# larson.net
KiCad netlist of a schematic drawn in EAGLE
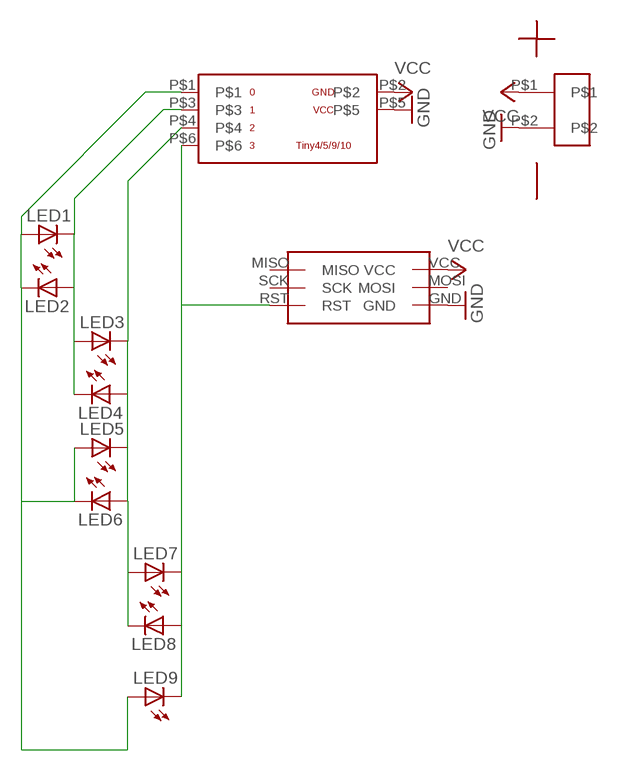
[diagram p0: schematic, sheet 1]

(export (version "E")
  (design (tool "Eeschema 10.0.6"))
  (components
    (comp (ref "LED1")
      (value "LED3MM")
      (footprint "eagle-import:LED3MM")
      (libsource (lib "eagle-import") (part "LED3MM"))
    )
    (comp (ref "LED2")
      (value "LED3MM")
      (footprint "eagle-import:LED3MM")
      (libsource (lib "eagle-import") (part "LED3MM"))
    )
    (comp (ref "LED3")
      (value "LED3MM")
      (footprint "eagle-import:LED3MM")
      (libsource (lib "eagle-import") (part "LED3MM"))
    )
    (comp (ref "LED4")
      (value "LED3MM")
      (footprint "eagle-import:LED3MM")
      (libsource (lib "eagle-import") (part "LED3MM"))
    )
    (comp (ref "LED5")
      (value "LED3MM")
      (footprint "eagle-import:LED3MM")
      (libsource (lib "eagle-import") (part "LED3MM"))
    )
    (comp (ref "LED6")
      (value "LED3MM")
      (footprint "eagle-import:LED3MM")
      (libsource (lib "eagle-import") (part "LED3MM"))
    )
    (comp (ref "LED7")
      (value "LED3MM")
      (footprint "eagle-import:LED3MM")
      (libsource (lib "eagle-import") (part "LED3MM"))
    )
    (comp (ref "LED8")
      (value "LED3MM")
      (footprint "eagle-import:LED3MM")
      (libsource (lib "eagle-import") (part "LED3MM"))
    )
    (comp (ref "LED9")
      (value "LED3MM")
      (footprint "eagle-import:LED3MM")
      (libsource (lib "eagle-import") (part "LED3MM"))
    )
    (comp (ref "U$1")
      (value "ATTINY4/5/9/10")
      (footprint "eagle-import:SOT23-6ST1")
      (libsource (lib "eagle-import") (part "ATTINY4/5/9/10"))
    )
    (comp (ref "U$2")
      (value "POWER_PINS")
      (footprint "eagle-import:POWER_PINS")
      (libsource (lib "eagle-import") (part "POWER_PINS"))
    )
    (comp (ref "U$3")
      (value "AVR_ISP_6_PIN_1X6_SMT_CONTACT_BIG")
      (footprint "eagle-import:CONTACT_ISP_PROGRAMMER_1X6_ATMEL")
      (libsource (lib "eagle-import") (part "AVR_ISP_6_PIN_1X6_SMT_CONTACT_BIG"))
    )
  )
  (nets
    (net (code "1") (name "GND") (class "Default")
      (node (ref "U$1") (pin "P$5") (pinfunction "P$5_P$5") (pintype "bidirectional"))
      (node (ref "U$2") (pin "P$2") (pinfunction "P$2_P$2") (pintype "bidirectional"))
      (node (ref "U$3") (pin "GND") (pinfunction "GND_GND") (pintype "bidirectional"))
    )
    (net (code "2") (name "Net-(LED1-C)") (class "Default")
      (node (ref "LED1") (pin "K") (pinfunction "C_K") (pintype "passive"))
      (node (ref "LED2") (pin "A") (pinfunction "A_A") (pintype "passive"))
      (node (ref "LED3") (pin "A") (pinfunction "A_A") (pintype "passive"))
      (node (ref "LED4") (pin "K") (pinfunction "C_K") (pintype "passive"))
      (node (ref "U$1") (pin "P$3") (pinfunction "P$3_P$3") (pintype "bidirectional"))
    )
    (net (code "3") (name "Net-(LED2-C)") (class "Default")
      (node (ref "LED1") (pin "A") (pinfunction "A_A") (pintype "passive"))
      (node (ref "LED2") (pin "K") (pinfunction "C_K") (pintype "passive"))
      (node (ref "LED5") (pin "A") (pinfunction "A_A") (pintype "passive"))
      (node (ref "LED6") (pin "K") (pinfunction "C_K") (pintype "passive"))
      (node (ref "LED9") (pin "A") (pinfunction "A_A") (pintype "passive"))
      (node (ref "U$1") (pin "P$1") (pinfunction "P$1_P$1") (pintype "bidirectional"))
    )
    (net (code "4") (name "Net-(LED3-C)") (class "Default")
      (node (ref "LED3") (pin "K") (pinfunction "C_K") (pintype "passive"))
      (node (ref "LED4") (pin "A") (pinfunction "A_A") (pintype "passive"))
      (node (ref "LED5") (pin "K") (pinfunction "C_K") (pintype "passive"))
      (node (ref "LED6") (pin "A") (pinfunction "A_A") (pintype "passive"))
      (node (ref "LED7") (pin "A") (pinfunction "A_A") (pintype "passive"))
      (node (ref "LED8") (pin "K") (pinfunction "C_K") (pintype "passive"))
      (node (ref "U$1") (pin "P$4") (pinfunction "P$4_P$4") (pintype "bidirectional"))
    )
    (net (code "5") (name "Net-(LED7-C)") (class "Default")
      (node (ref "LED7") (pin "K") (pinfunction "C_K") (pintype "passive"))
      (node (ref "LED8") (pin "A") (pinfunction "A_A") (pintype "passive"))
      (node (ref "LED9") (pin "K") (pinfunction "C_K") (pintype "passive"))
      (node (ref "U$1") (pin "P$6") (pinfunction "P$6_P$6") (pintype "bidirectional"))
      (node (ref "U$3") (pin "RST") (pinfunction "RST_RST") (pintype "bidirectional"))
    )
    (net (code "6") (name "VCC") (class "Default")
      (node (ref "U$1") (pin "P$2") (pinfunction "P$2_P$2") (pintype "bidirectional"))
      (node (ref "U$2") (pin "P$1") (pinfunction "P$1_P$1") (pintype "bidirectional"))
      (node (ref "U$3") (pin "VCC") (pinfunction "VCC_VCC") (pintype "bidirectional"))
    )
    (net (code "7") (name "unconnected-(U$3-PadMISO)") (class "Default")
      (node (ref "U$3") (pin "MISO") (pinfunction "MISO_MISO") (pintype "bidirectional"))
    )
    (net (code "8") (name "unconnected-(U$3-PadMOSI)") (class "Default")
      (node (ref "U$3") (pin "MOSI") (pinfunction "MOSI_MOSI") (pintype "bidirectional"))
    )
    (net (code "9") (name "unconnected-(U$3-PadSCK)") (class "Default")
      (node (ref "U$3") (pin "SCK") (pinfunction "SCK_SCK") (pintype "bidirectional"))
    )
  )
)
